# ESCapemk4.net
KiCad netlist of a schematic drawn in EAGLE
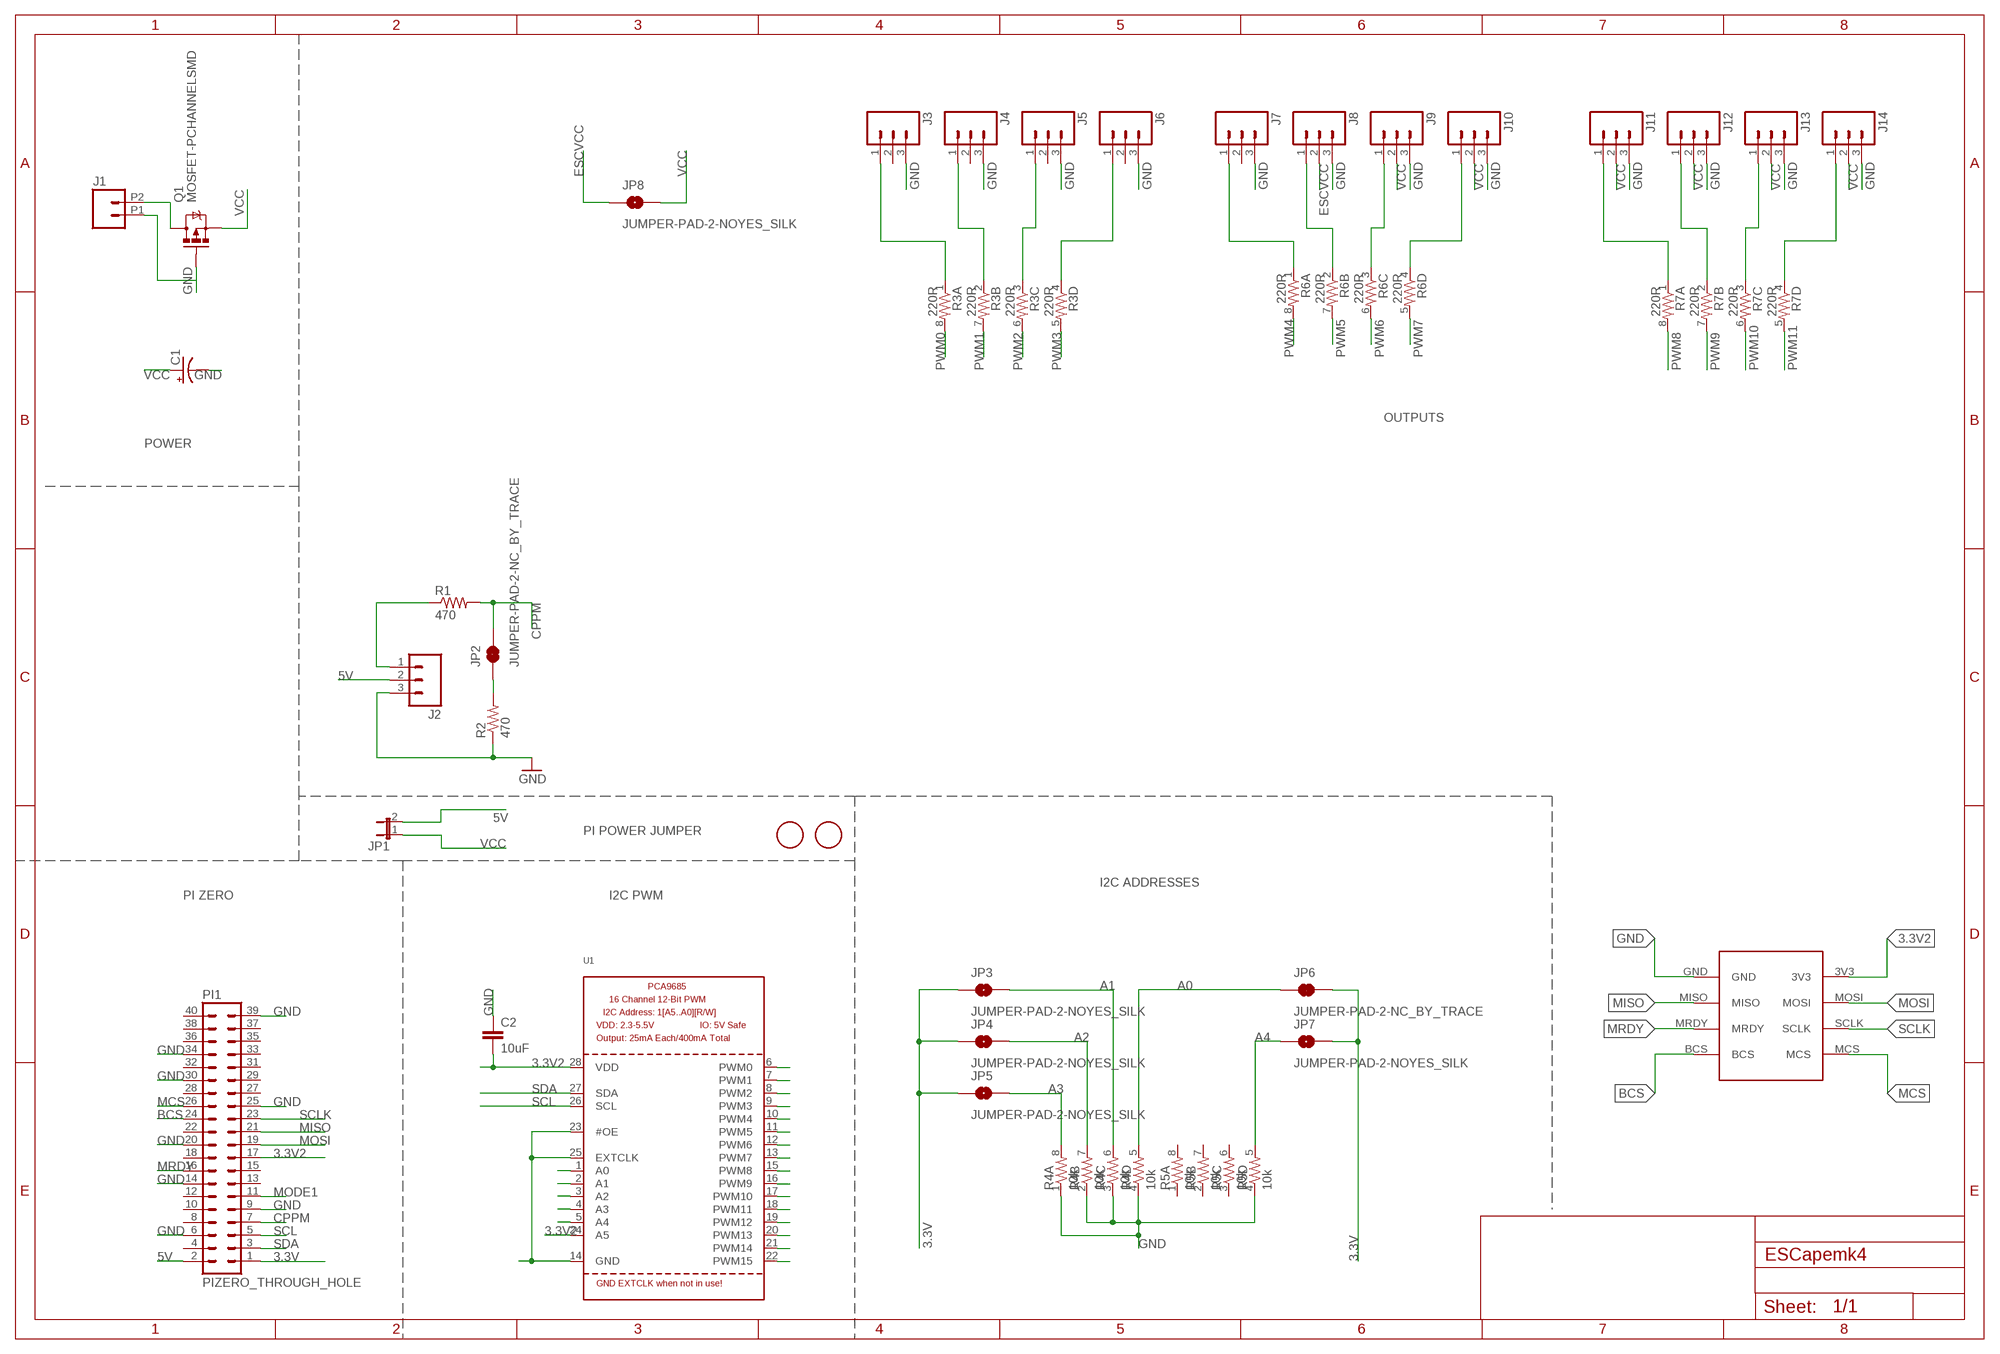
[diagram p0: schematic, sheet 1]

(export (version "E")
  (design (tool "Eeschema 10.0.6"))
  (components
    (comp (ref "C1")
      (value "CAP_POLPTH1")
      (footprint "eagle-import:CPOL-RADIAL-100UF-25V")
      (libsource (lib "eagle-import") (part "CAP_POLPTH1"))
    )
    (comp (ref "C2")
      (value "10uF")
      (footprint "eagle-import:0805")
      (libsource (lib "eagle-import") (part "CAP0805"))
    )
    (comp (ref "FID1")
      (value "FIDUCIAL")
      (footprint "eagle-import:FIDUCIAL_1MM")
      (libsource (lib "eagle-import") (part "FIDUCIAL"))
    )
    (comp (ref "FID2")
      (value "FIDUCIAL")
      (footprint "eagle-import:FIDUCIAL_1MM")
      (libsource (lib "eagle-import") (part "FIDUCIAL"))
    )
    (comp (ref "J1")
      (value "M022.54MM_SCREWTERM")
      (footprint "eagle-import:1X02_2.54_SCREWTERM")
      (libsource (lib "eagle-import") (part "M022.54MM_SCREWTERM"))
    )
    (comp (ref "J2")
      (value "M03LOCK")
      (footprint "eagle-import:1X03_LOCK")
      (libsource (lib "eagle-import") (part "M03LOCK"))
    )
    (comp (ref "J3")
      (value "M03LOCK")
      (footprint "eagle-import:1X03_LOCK")
      (libsource (lib "eagle-import") (part "M03LOCK"))
    )
    (comp (ref "J4")
      (value "M03LOCK")
      (footprint "eagle-import:1X03_LOCK")
      (libsource (lib "eagle-import") (part "M03LOCK"))
    )
    (comp (ref "J5")
      (value "M03LOCK")
      (footprint "eagle-import:1X03_LOCK")
      (libsource (lib "eagle-import") (part "M03LOCK"))
    )
    (comp (ref "J6")
      (value "M03LOCK")
      (footprint "eagle-import:1X03_LOCK")
      (libsource (lib "eagle-import") (part "M03LOCK"))
    )
    (comp (ref "J7")
      (value "M03LOCK")
      (footprint "eagle-import:1X03_LOCK")
      (libsource (lib "eagle-import") (part "M03LOCK"))
    )
    (comp (ref "J8")
      (value "M03LOCK")
      (footprint "eagle-import:1X03_LOCK")
      (libsource (lib "eagle-import") (part "M03LOCK"))
    )
    (comp (ref "J9")
      (value "M03LOCK")
      (footprint "eagle-import:1X03_LOCK")
      (libsource (lib "eagle-import") (part "M03LOCK"))
    )
    (comp (ref "J10")
      (value "M03LOCK")
      (footprint "eagle-import:1X03_LOCK")
      (libsource (lib "eagle-import") (part "M03LOCK"))
    )
    (comp (ref "J11")
      (value "M03LOCK")
      (footprint "eagle-import:1X03_LOCK")
      (libsource (lib "eagle-import") (part "M03LOCK"))
    )
    (comp (ref "J12")
      (value "M03LOCK")
      (footprint "eagle-import:1X03_LOCK")
      (libsource (lib "eagle-import") (part "M03LOCK"))
    )
    (comp (ref "J13")
      (value "M03LOCK")
      (footprint "eagle-import:1X03_LOCK")
      (libsource (lib "eagle-import") (part "M03LOCK"))
    )
    (comp (ref "J14")
      (value "M03LOCK")
      (footprint "eagle-import:1X03_LOCK")
      (libsource (lib "eagle-import") (part "M03LOCK"))
    )
    (comp (ref "JP1")
      (value "JUMPER-2PTH_LOCK")
      (footprint "eagle-import:1X02_LOCK")
      (libsource (lib "eagle-import") (part "JUMPER-2PTH_LOCK"))
    )
    (comp (ref "JP2")
      (value "JUMPER-PAD-2-NC_BY_TRACE")
      (footprint "eagle-import:PAD-JUMPER-2-NC_BY_TRACE_YES_SILK")
      (libsource (lib "eagle-import") (part "JUMPER-PAD-2-NC_BY_TRACE"))
    )
    (comp (ref "JP3")
      (value "JUMPER-PAD-2-NOYES_SILK")
      (footprint "eagle-import:PAD-JUMPER-2-NO_YES_SILK")
      (libsource (lib "eagle-import") (part "JUMPER-PAD-2-NOYES_SILK"))
    )
    (comp (ref "JP4")
      (value "JUMPER-PAD-2-NOYES_SILK")
      (footprint "eagle-import:PAD-JUMPER-2-NO_YES_SILK")
      (libsource (lib "eagle-import") (part "JUMPER-PAD-2-NOYES_SILK"))
    )
    (comp (ref "JP5")
      (value "JUMPER-PAD-2-NOYES_SILK")
      (footprint "eagle-import:PAD-JUMPER-2-NO_YES_SILK")
      (libsource (lib "eagle-import") (part "JUMPER-PAD-2-NOYES_SILK"))
    )
    (comp (ref "JP6")
      (value "JUMPER-PAD-2-NC_BY_TRACE")
      (footprint "eagle-import:PAD-JUMPER-2-NC_BY_TRACE_YES_SILK")
      (libsource (lib "eagle-import") (part "JUMPER-PAD-2-NC_BY_TRACE"))
    )
    (comp (ref "JP7")
      (value "JUMPER-PAD-2-NOYES_SILK")
      (footprint "eagle-import:PAD-JUMPER-2-NO_YES_SILK")
      (libsource (lib "eagle-import") (part "JUMPER-PAD-2-NOYES_SILK"))
    )
    (comp (ref "JP8")
      (value "JUMPER-PAD-2-NOYES_SILK")
      (footprint "eagle-import:PAD-JUMPER-2-NO_YES_SILK")
      (libsource (lib "eagle-import") (part "JUMPER-PAD-2-NOYES_SILK"))
    )
    (comp (ref "PI1")
      (value "PIZERO_THROUGH_HOLE")
      (footprint "eagle-import:PIZERO_THOUGH_HOLE")
      (libsource (lib "eagle-import") (part "PIZERO_THROUGH_HOLE"))
    )
    (comp (ref "Q1")
      (value "MOSFET-PCHANNELSMD")
      (footprint "eagle-import:SOT23-3")
      (libsource (lib "eagle-import") (part "MOSFET-PCHANNELSMD"))
    )
    (comp (ref "R1")
      (value "470")
      (footprint "eagle-import:0805")
      (libsource (lib "eagle-import") (part "RESISTOR0805-RES"))
    )
    (comp (ref "R2")
      (value "470")
      (footprint "eagle-import:0805")
      (libsource (lib "eagle-import") (part "RESISTOR0805-RES"))
    )
    (comp (ref "R3")
      (value "220R")
      (footprint "eagle-import:0603-ARV")
      (libsource (lib "eagle-import") (part "RESISTOR-ARRAY0603-ARV"))
    )
    (comp (ref "R4")
      (value "10k")
      (footprint "eagle-import:0603-ARV")
      (libsource (lib "eagle-import") (part "RESISTOR-ARRAY0603-ARV"))
    )
    (comp (ref "R5")
      (value "10k")
      (footprint "eagle-import:0603-ARV")
      (libsource (lib "eagle-import") (part "RESISTOR-ARRAY0603-ARV"))
    )
    (comp (ref "R6")
      (value "220R")
      (footprint "eagle-import:0603-ARV")
      (libsource (lib "eagle-import") (part "RESISTOR-ARRAY0603-ARV"))
    )
    (comp (ref "R7")
      (value "220R")
      (footprint "eagle-import:0603-ARV")
      (libsource (lib "eagle-import") (part "RESISTOR-ARRAY0603-ARV"))
    )
    (comp (ref "U$1")
      (value "2X4PADS")
      (footprint "eagle-import:2X4PADS")
      (libsource (lib "eagle-import") (part "2X4PADS"))
    )
    (comp (ref "U1")
      (value "PCA9685")
      (footprint "eagle-import:TSSOP28")
      (libsource (lib "eagle-import") (part "PCA9685"))
    )
  )
  (nets
    (net (code "1") (name "/3.3V") (class "Default")
      (node (ref "JP3") (pin "1") (pinfunction "1_1") (pintype "passive"))
      (node (ref "JP4") (pin "1") (pinfunction "1_1") (pintype "passive"))
      (node (ref "JP5") (pin "1") (pinfunction "1_1") (pintype "passive"))
      (node (ref "JP6") (pin "2") (pinfunction "2_2") (pintype "passive"))
      (node (ref "JP7") (pin "2") (pinfunction "2_2") (pintype "passive"))
      (node (ref "PI1") (pin "1") (pinfunction "1_1") (pintype "passive"))
    )
    (net (code "2") (name "/5V") (class "Default")
      (node (ref "J2") (pin "2") (pinfunction "2_2") (pintype "passive"))
      (node (ref "JP1") (pin "2") (pinfunction "2_2") (pintype "passive"))
      (node (ref "PI1") (pin "2") (pinfunction "2_2") (pintype "passive"))
    )
    (net (code "3") (name "/A0") (class "Default")
      (node (ref "JP6") (pin "1") (pinfunction "1_1") (pintype "passive"))
      (node (ref "R4") (pin "5") (pinfunction "2_5") (pintype "passive"))
      (node (ref "U1") (pin "1") (pinfunction "A0_1") (pintype "bidirectional"))
    )
    (net (code "4") (name "/A1") (class "Default")
      (node (ref "JP3") (pin "2") (pinfunction "2_2") (pintype "passive"))
      (node (ref "R4") (pin "6") (pinfunction "2_6") (pintype "passive"))
      (node (ref "U1") (pin "2") (pinfunction "A1_2") (pintype "bidirectional"))
    )
    (net (code "5") (name "/A2") (class "Default")
      (node (ref "JP4") (pin "2") (pinfunction "2_2") (pintype "passive"))
      (node (ref "R4") (pin "7") (pinfunction "2_7") (pintype "passive"))
      (node (ref "U1") (pin "3") (pinfunction "A2_3") (pintype "bidirectional"))
    )
    (net (code "6") (name "/A3") (class "Default")
      (node (ref "JP5") (pin "2") (pinfunction "2_2") (pintype "passive"))
      (node (ref "R4") (pin "8") (pinfunction "2_8") (pintype "passive"))
      (node (ref "U1") (pin "4") (pinfunction "A3_4") (pintype "bidirectional"))
    )
    (net (code "7") (name "/A4") (class "Default")
      (node (ref "JP7") (pin "1") (pinfunction "1_1") (pintype "passive"))
      (node (ref "R5") (pin "5") (pinfunction "2_5") (pintype "passive"))
      (node (ref "U1") (pin "5") (pinfunction "A4_5") (pintype "bidirectional"))
    )
    (net (code "8") (name "/CPPM") (class "Default")
      (node (ref "JP2") (pin "2") (pinfunction "2_2") (pintype "passive"))
      (node (ref "PI1") (pin "7") (pinfunction "7_7") (pintype "passive"))
      (node (ref "R1") (pin "2") (pinfunction "2_2") (pintype "passive"))
    )
    (net (code "9") (name "/ESCVCC") (class "Default")
      (node (ref "J8") (pin "2") (pinfunction "2_2") (pintype "passive"))
      (node (ref "JP8") (pin "1") (pinfunction "1_1") (pintype "passive"))
    )
    (net (code "10") (name "/MODE1") (class "Default")
      (node (ref "PI1") (pin "11") (pinfunction "11_11") (pintype "passive"))
    )
    (net (code "11") (name "/PWM0") (class "Default")
      (node (ref "R3") (pin "8") (pinfunction "2_8") (pintype "passive"))
      (node (ref "U1") (pin "6") (pinfunction "PWM0_6") (pintype "output"))
    )
    (net (code "12") (name "/PWM1") (class "Default")
      (node (ref "R3") (pin "7") (pinfunction "2_7") (pintype "passive"))
      (node (ref "U1") (pin "7") (pinfunction "PWM1_7") (pintype "output"))
    )
    (net (code "13") (name "/PWM2") (class "Default")
      (node (ref "R3") (pin "6") (pinfunction "2_6") (pintype "passive"))
      (node (ref "U1") (pin "8") (pinfunction "PWM2_8") (pintype "output"))
    )
    (net (code "14") (name "/PWM3") (class "Default")
      (node (ref "R3") (pin "5") (pinfunction "2_5") (pintype "passive"))
      (node (ref "U1") (pin "9") (pinfunction "PWM3_9") (pintype "output"))
    )
    (net (code "15") (name "/PWM4") (class "Default")
      (node (ref "R6") (pin "8") (pinfunction "2_8") (pintype "passive"))
      (node (ref "U1") (pin "10") (pinfunction "PWM4_10") (pintype "output"))
    )
    (net (code "16") (name "/PWM5") (class "Default")
      (node (ref "R6") (pin "7") (pinfunction "2_7") (pintype "passive"))
      (node (ref "U1") (pin "11") (pinfunction "PWM5_11") (pintype "output"))
    )
    (net (code "17") (name "/PWM6") (class "Default")
      (node (ref "R6") (pin "6") (pinfunction "2_6") (pintype "passive"))
      (node (ref "U1") (pin "12") (pinfunction "PWM6_12") (pintype "output"))
    )
    (net (code "18") (name "/PWM7") (class "Default")
      (node (ref "R6") (pin "5") (pinfunction "2_5") (pintype "passive"))
      (node (ref "U1") (pin "13") (pinfunction "PWM7_13") (pintype "output"))
    )
    (net (code "19") (name "/PWM8") (class "Default")
      (node (ref "R7") (pin "8") (pinfunction "2_8") (pintype "passive"))
      (node (ref "U1") (pin "15") (pinfunction "PWM8_15") (pintype "output"))
    )
    (net (code "20") (name "/PWM9") (class "Default")
      (node (ref "R7") (pin "7") (pinfunction "2_7") (pintype "passive"))
      (node (ref "U1") (pin "16") (pinfunction "PWM9_16") (pintype "output"))
    )
    (net (code "21") (name "/PWM10") (class "Default")
      (node (ref "R7") (pin "6") (pinfunction "2_6") (pintype "passive"))
      (node (ref "U1") (pin "17") (pinfunction "PWM10_17") (pintype "output"))
    )
    (net (code "22") (name "/PWM11") (class "Default")
      (node (ref "R7") (pin "5") (pinfunction "2_5") (pintype "passive"))
      (node (ref "U1") (pin "18") (pinfunction "PWM11_18") (pintype "output"))
    )
    (net (code "23") (name "/SCL") (class "Default")
      (node (ref "PI1") (pin "5") (pinfunction "5_5") (pintype "passive"))
      (node (ref "U1") (pin "26") (pinfunction "SCL_26") (pintype "bidirectional"))
    )
    (net (code "24") (name "/SDA") (class "Default")
      (node (ref "PI1") (pin "3") (pinfunction "3_3") (pintype "passive"))
      (node (ref "U1") (pin "27") (pinfunction "SDA_27") (pintype "bidirectional"))
    )
    (net (code "25") (name "/VCC") (class "Default")
      (node (ref "C1") (pin "1") (pinfunction "+_1") (pintype "passive"))
      (node (ref "J10") (pin "2") (pinfunction "2_2") (pintype "passive"))
      (node (ref "J11") (pin "2") (pinfunction "2_2") (pintype "passive"))
      (node (ref "J12") (pin "2") (pinfunction "2_2") (pintype "passive"))
      (node (ref "J13") (pin "2") (pinfunction "2_2") (pintype "passive"))
      (node (ref "J14") (pin "2") (pinfunction "2_2") (pintype "passive"))
      (node (ref "J9") (pin "2") (pinfunction "2_2") (pintype "passive"))
      (node (ref "JP1") (pin "1") (pinfunction "1_1") (pintype "passive"))
      (node (ref "JP8") (pin "2") (pinfunction "2_2") (pintype "passive"))
      (node (ref "Q1") (pin "2") (pinfunction "S_2") (pintype "passive"))
    )
    (net (code "26") (name "3.3V2") (class "Default")
      (node (ref "C2") (pin "2") (pinfunction "2_2") (pintype "passive"))
      (node (ref "PI1") (pin "17") (pinfunction "17_17") (pintype "passive"))
      (node (ref "U$1") (pin "3V3") (pinfunction "3V3_3V3") (pintype "bidirectional"))
      (node (ref "U1") (pin "24") (pinfunction "A5_24") (pintype "bidirectional"))
      (node (ref "U1") (pin "28") (pinfunction "VDD_28") (pintype "power_in"))
    )
    (net (code "27") (name "BCS") (class "Default")
      (node (ref "PI1") (pin "24") (pinfunction "24_24") (pintype "passive"))
      (node (ref "U$1") (pin "BCS") (pinfunction "BCS_BCS") (pintype "bidirectional"))
    )
    (net (code "28") (name "GND") (class "Default")
      (node (ref "C1") (pin "2") (pinfunction "-_2") (pintype "passive"))
      (node (ref "C2") (pin "1") (pinfunction "1_1") (pintype "passive"))
      (node (ref "J1") (pin "P1") (pinfunction "1_P1") (pintype "passive"))
      (node (ref "J10") (pin "3") (pinfunction "3_3") (pintype "passive"))
      (node (ref "J11") (pin "3") (pinfunction "3_3") (pintype "passive"))
      (node (ref "J12") (pin "3") (pinfunction "3_3") (pintype "passive"))
      (node (ref "J13") (pin "3") (pinfunction "3_3") (pintype "passive"))
      (node (ref "J14") (pin "3") (pinfunction "3_3") (pintype "passive"))
      (node (ref "J2") (pin "3") (pinfunction "3_3") (pintype "passive"))
      (node (ref "J3") (pin "3") (pinfunction "3_3") (pintype "passive"))
      (node (ref "J4") (pin "3") (pinfunction "3_3") (pintype "passive"))
      (node (ref "J5") (pin "3") (pinfunction "3_3") (pintype "passive"))
      (node (ref "J6") (pin "3") (pinfunction "3_3") (pintype "passive"))
      (node (ref "J7") (pin "3") (pinfunction "3_3") (pintype "passive"))
      (node (ref "J8") (pin "3") (pinfunction "3_3") (pintype "passive"))
      (node (ref "J9") (pin "3") (pinfunction "3_3") (pintype "passive"))
      (node (ref "PI1") (pin "14") (pinfunction "14_14") (pintype "passive"))
      (node (ref "PI1") (pin "20") (pinfunction "20_20") (pintype "passive"))
      (node (ref "PI1") (pin "25") (pinfunction "25_25") (pintype "passive"))
      (node (ref "PI1") (pin "30") (pinfunction "30_30") (pintype "passive"))
      (node (ref "PI1") (pin "34") (pinfunction "34_34") (pintype "passive"))
      (node (ref "PI1") (pin "39") (pinfunction "39_39") (pintype "passive"))
      (node (ref "PI1") (pin "6") (pinfunction "6_6") (pintype "passive"))
      (node (ref "PI1") (pin "9") (pinfunction "9_9") (pintype "passive"))
      (node (ref "Q1") (pin "1") (pinfunction "G_1") (pintype "passive"))
      (node (ref "R2") (pin "1") (pinfunction "1_1") (pintype "passive"))
      (node (ref "R4") (pin "1") (pinfunction "1_1") (pintype "passive"))
      (node (ref "R4") (pin "2") (pinfunction "1_2") (pintype "passive"))
      (node (ref "R4") (pin "3") (pinfunction "1_3") (pintype "passive"))
      (node (ref "R4") (pin "4") (pinfunction "1_4") (pintype "passive"))
      (node (ref "R5") (pin "4") (pinfunction "1_4") (pintype "passive"))
      (node (ref "U$1") (pin "GND") (pinfunction "GND_GND") (pintype "bidirectional"))
      (node (ref "U1") (pin "14") (pinfunction "GND_14") (pintype "power_in"))
      (node (ref "U1") (pin "23") (pinfunction "#OE_23") (pintype "input"))
      (node (ref "U1") (pin "25") (pinfunction "EXTCLK_25") (pintype "input"))
    )
    (net (code "29") (name "MCS") (class "Default")
      (node (ref "PI1") (pin "26") (pinfunction "26_26") (pintype "passive"))
      (node (ref "U$1") (pin "MCS") (pinfunction "MCS_MCS") (pintype "bidirectional"))
    )
    (net (code "30") (name "MISO") (class "Default")
      (node (ref "PI1") (pin "21") (pinfunction "21_21") (pintype "passive"))
      (node (ref "U$1") (pin "MISO") (pinfunction "MISO_MISO") (pintype "bidirectional"))
    )
    (net (code "31") (name "MOSI") (class "Default")
      (node (ref "PI1") (pin "19") (pinfunction "19_19") (pintype "passive"))
      (node (ref "U$1") (pin "MOSI") (pinfunction "MOSI_MOSI") (pintype "bidirectional"))
    )
    (net (code "32") (name "MRDY") (class "Default")
      (node (ref "PI1") (pin "16") (pinfunction "16_16") (pintype "passive"))
      (node (ref "U$1") (pin "MRDY") (pinfunction "MRDY_MRDY") (pintype "bidirectional"))
    )
    (net (code "33") (name "Net-(J1-2)") (class "Default")
      (node (ref "J1") (pin "P2") (pinfunction "2_P2") (pintype "passive"))
      (node (ref "Q1") (pin "3") (pinfunction "D_3") (pintype "passive"))
    )
    (net (code "34") (name "Net-(J2-Pad1)") (class "Default")
      (node (ref "J2") (pin "1") (pinfunction "1_1") (pintype "passive"))
      (node (ref "R1") (pin "1") (pinfunction "1_1") (pintype "passive"))
    )
    (net (code "35") (name "Net-(J3-Pad1)") (class "Default")
      (node (ref "J3") (pin "1") (pinfunction "1_1") (pintype "passive"))
      (node (ref "R3") (pin "1") (pinfunction "1_1") (pintype "passive"))
    )
    (net (code "36") (name "Net-(J7-Pad1)") (class "Default")
      (node (ref "J7") (pin "1") (pinfunction "1_1") (pintype "passive"))
      (node (ref "R6") (pin "1") (pinfunction "1_1") (pintype "passive"))
    )
    (net (code "37") (name "Net-(J11-Pad1)") (class "Default")
      (node (ref "J11") (pin "1") (pinfunction "1_1") (pintype "passive"))
      (node (ref "R7") (pin "1") (pinfunction "1_1") (pintype "passive"))
    )
    (net (code "38") (name "Net-(JP2-Pad1)") (class "Default")
      (node (ref "JP2") (pin "1") (pinfunction "1_1") (pintype "passive"))
      (node (ref "R2") (pin "2") (pinfunction "2_2") (pintype "passive"))
    )
    (net (code "39") (name "Net-(R3B-1)") (class "Default")
      (node (ref "J4") (pin "1") (pinfunction "1_1") (pintype "passive"))
      (node (ref "R3") (pin "2") (pinfunction "1_2") (pintype "passive"))
    )
    (net (code "40") (name "Net-(R3C-1)") (class "Default")
      (node (ref "J5") (pin "1") (pinfunction "1_1") (pintype "passive"))
      (node (ref "R3") (pin "3") (pinfunction "1_3") (pintype "passive"))
    )
    (net (code "41") (name "Net-(R3D-1)") (class "Default")
      (node (ref "J6") (pin "1") (pinfunction "1_1") (pintype "passive"))
      (node (ref "R3") (pin "4") (pinfunction "1_4") (pintype "passive"))
    )
    (net (code "42") (name "Net-(R6B-1)") (class "Default")
      (node (ref "J8") (pin "1") (pinfunction "1_1") (pintype "passive"))
      (node (ref "R6") (pin "2") (pinfunction "1_2") (pintype "passive"))
    )
    (net (code "43") (name "Net-(R6C-1)") (class "Default")
      (node (ref "J9") (pin "1") (pinfunction "1_1") (pintype "passive"))
      (node (ref "R6") (pin "3") (pinfunction "1_3") (pintype "passive"))
    )
    (net (code "44") (name "Net-(R6D-1)") (class "Default")
      (node (ref "J10") (pin "1") (pinfunction "1_1") (pintype "passive"))
      (node (ref "R6") (pin "4") (pinfunction "1_4") (pintype "passive"))
    )
    (net (code "45") (name "Net-(R7B-1)") (class "Default")
      (node (ref "J12") (pin "1") (pinfunction "1_1") (pintype "passive"))
      (node (ref "R7") (pin "2") (pinfunction "1_2") (pintype "passive"))
    )
    (net (code "46") (name "Net-(R7C-1)") (class "Default")
      (node (ref "J13") (pin "1") (pinfunction "1_1") (pintype "passive"))
      (node (ref "R7") (pin "3") (pinfunction "1_3") (pintype "passive"))
    )
    (net (code "47") (name "Net-(R7D-1)") (class "Default")
      (node (ref "J14") (pin "1") (pinfunction "1_1") (pintype "passive"))
      (node (ref "R7") (pin "4") (pinfunction "1_4") (pintype "passive"))
    )
    (net (code "48") (name "SCLK") (class "Default")
      (node (ref "PI1") (pin "23") (pinfunction "23_23") (pintype "passive"))
      (node (ref "U$1") (pin "SCLK") (pinfunction "SCLK_SCLK") (pintype "bidirectional"))
    )
    (net (code "49") (name "unconnected-(J3-Pad2)") (class "Default")
      (node (ref "J3") (pin "2") (pinfunction "2_2") (pintype "passive"))
    )
    (net (code "50") (name "unconnected-(J4-Pad2)") (class "Default")
      (node (ref "J4") (pin "2") (pinfunction "2_2") (pintype "passive"))
    )
    (net (code "51") (name "unconnected-(J5-Pad2)") (class "Default")
      (node (ref "J5") (pin "2") (pinfunction "2_2") (pintype "passive"))
    )
    (net (code "52") (name "unconnected-(J6-Pad2)") (class "Default")
      (node (ref "J6") (pin "2") (pinfunction "2_2") (pintype "passive"))
    )
    (net (code "53") (name "unconnected-(J7-Pad2)") (class "Default")
      (node (ref "J7") (pin "2") (pinfunction "2_2") (pintype "passive"))
    )
    (net (code "54") (name "unconnected-(PI1-Pad4)") (class "Default")
      (node (ref "PI1") (pin "4") (pinfunction "4_4") (pintype "passive"))
    )
    (net (code "55") (name "unconnected-(PI1-Pad8)") (class "Default")
      (node (ref "PI1") (pin "8") (pinfunction "8_8") (pintype "passive"))
    )
    (net (code "56") (name "unconnected-(PI1-Pad10)") (class "Default")
      (node (ref "PI1") (pin "10") (pinfunction "10_10") (pintype "passive"))
    )
    (net (code "57") (name "unconnected-(PI1-Pad12)") (class "Default")
      (node (ref "PI1") (pin "12") (pinfunction "12_12") (pintype "passive"))
    )
    (net (code "58") (name "unconnected-(PI1-Pad13)") (class "Default")
      (node (ref "PI1") (pin "13") (pinfunction "13_13") (pintype "passive"))
    )
    (net (code "59") (name "unconnected-(PI1-Pad15)") (class "Default")
      (node (ref "PI1") (pin "15") (pinfunction "15_15") (pintype "passive"))
    )
    (net (code "60") (name "unconnected-(PI1-Pad18)") (class "Default")
      (node (ref "PI1") (pin "18") (pinfunction "18_18") (pintype "passive"))
    )
    (net (code "61") (name "unconnected-(PI1-Pad22)") (class "Default")
      (node (ref "PI1") (pin "22") (pinfunction "22_22") (pintype "passive"))
    )
    (net (code "62") (name "unconnected-(PI1-Pad27)") (class "Default")
      (node (ref "PI1") (pin "27") (pinfunction "27_27") (pintype "passive"))
    )
    (net (code "63") (name "unconnected-(PI1-Pad28)") (class "Default")
      (node (ref "PI1") (pin "28") (pinfunction "28_28") (pintype "passive"))
    )
    (net (code "64") (name "unconnected-(PI1-Pad29)") (class "Default")
      (node (ref "PI1") (pin "29") (pinfunction "29_29") (pintype "passive"))
    )
    (net (code "65") (name "unconnected-(PI1-Pad31)") (class "Default")
      (node (ref "PI1") (pin "31") (pinfunction "31_31") (pintype "passive"))
    )
    (net (code "66") (name "unconnected-(PI1-Pad32)") (class "Default")
      (node (ref "PI1") (pin "32") (pinfunction "32_32") (pintype "passive"))
    )
    (net (code "67") (name "unconnected-(PI1-Pad33)") (class "Default")
      (node (ref "PI1") (pin "33") (pinfunction "33_33") (pintype "passive"))
    )
    (net (code "68") (name "unconnected-(PI1-Pad35)") (class "Default")
      (node (ref "PI1") (pin "35") (pinfunction "35_35") (pintype "passive"))
    )
    (net (code "69") (name "unconnected-(PI1-Pad36)") (class "Default")
      (node (ref "PI1") (pin "36") (pinfunction "36_36") (pintype "passive"))
    )
    (net (code "70") (name "unconnected-(PI1-Pad37)") (class "Default")
      (node (ref "PI1") (pin "37") (pinfunction "37_37") (pintype "passive"))
    )
    (net (code "71") (name "unconnected-(PI1-Pad38)") (class "Default")
      (node (ref "PI1") (pin "38") (pinfunction "38_38") (pintype "passive"))
    )
    (net (code "72") (name "unconnected-(PI1-Pad40)") (class "Default")
      (node (ref "PI1") (pin "40") (pinfunction "40_40") (pintype "passive"))
    )
    (net (code "73") (name "unconnected-(R5-Pad1)") (class "Default")
      (node (ref "R5") (pin "1") (pinfunction "1_1") (pintype "passive"))
    )
    (net (code "74") (name "unconnected-(R5A-2-Pad8)") (class "Default")
      (node (ref "R5") (pin "8") (pinfunction "2_8") (pintype "passive"))
    )
    (net (code "75") (name "unconnected-(R5B-1-Pad2)") (class "Default")
      (node (ref "R5") (pin "2") (pinfunction "1_2") (pintype "passive"))
    )
    (net (code "76") (name "unconnected-(R5B-2-Pad7)") (class "Default")
      (node (ref "R5") (pin "7") (pinfunction "2_7") (pintype "passive"))
    )
    (net (code "77") (name "unconnected-(R5C-1-Pad3)") (class "Default")
      (node (ref "R5") (pin "3") (pinfunction "1_3") (pintype "passive"))
    )
    (net (code "78") (name "unconnected-(R5C-2-Pad6)") (class "Default")
      (node (ref "R5") (pin "6") (pinfunction "2_6") (pintype "passive"))
    )
    (net (code "79") (name "unconnected-(U1-PWM12-Pad19)") (class "Default")
      (node (ref "U1") (pin "19") (pinfunction "PWM12_19") (pintype "output"))
    )
    (net (code "80") (name "unconnected-(U1-PWM13-Pad20)") (class "Default")
      (node (ref "U1") (pin "20") (pinfunction "PWM13_20") (pintype "output"))
    )
    (net (code "81") (name "unconnected-(U1-PWM14-Pad21)") (class "Default")
      (node (ref "U1") (pin "21") (pinfunction "PWM14_21") (pintype "output"))
    )
    (net (code "82") (name "unconnected-(U1-PWM15-Pad22)") (class "Default")
      (node (ref "U1") (pin "22") (pinfunction "PWM15_22") (pintype "output"))
    )
  )
)
